# CPU_board_2_7.net
KiCad netlist of a schematic drawn in EAGLE
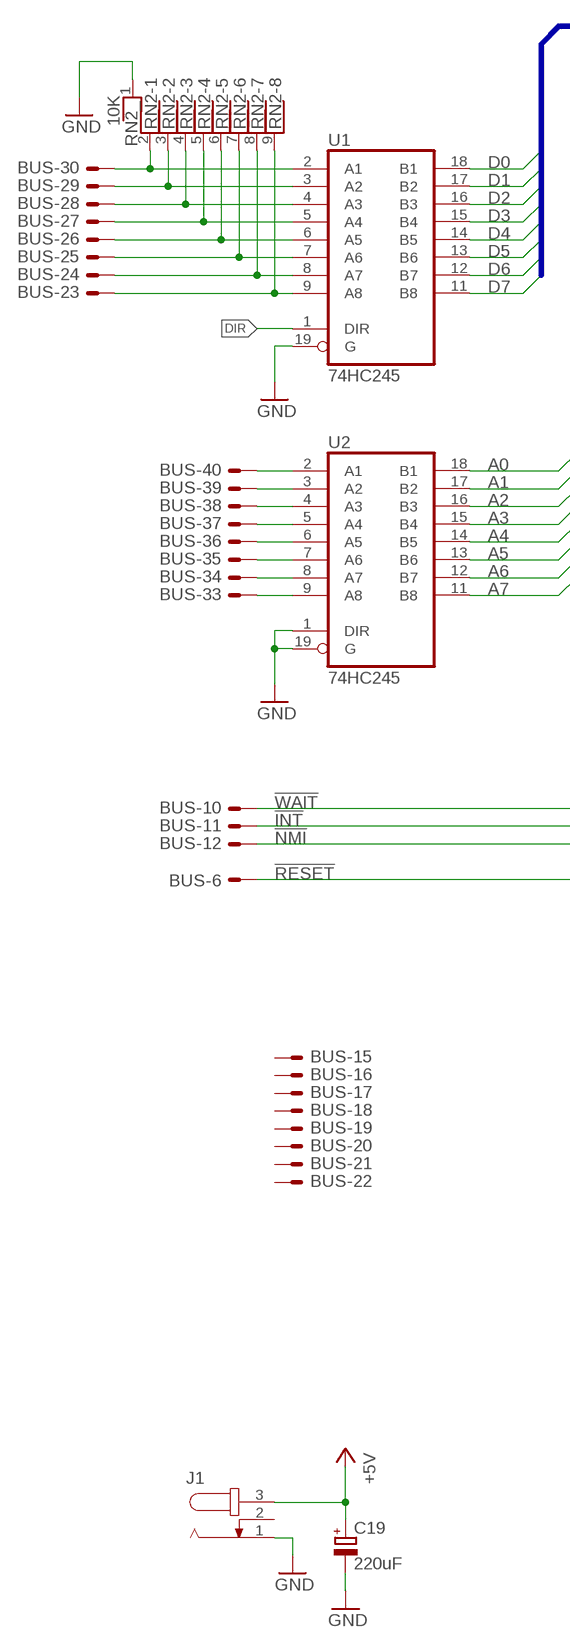
[diagram p0: schematic, sheet 1, part 1 of 2]
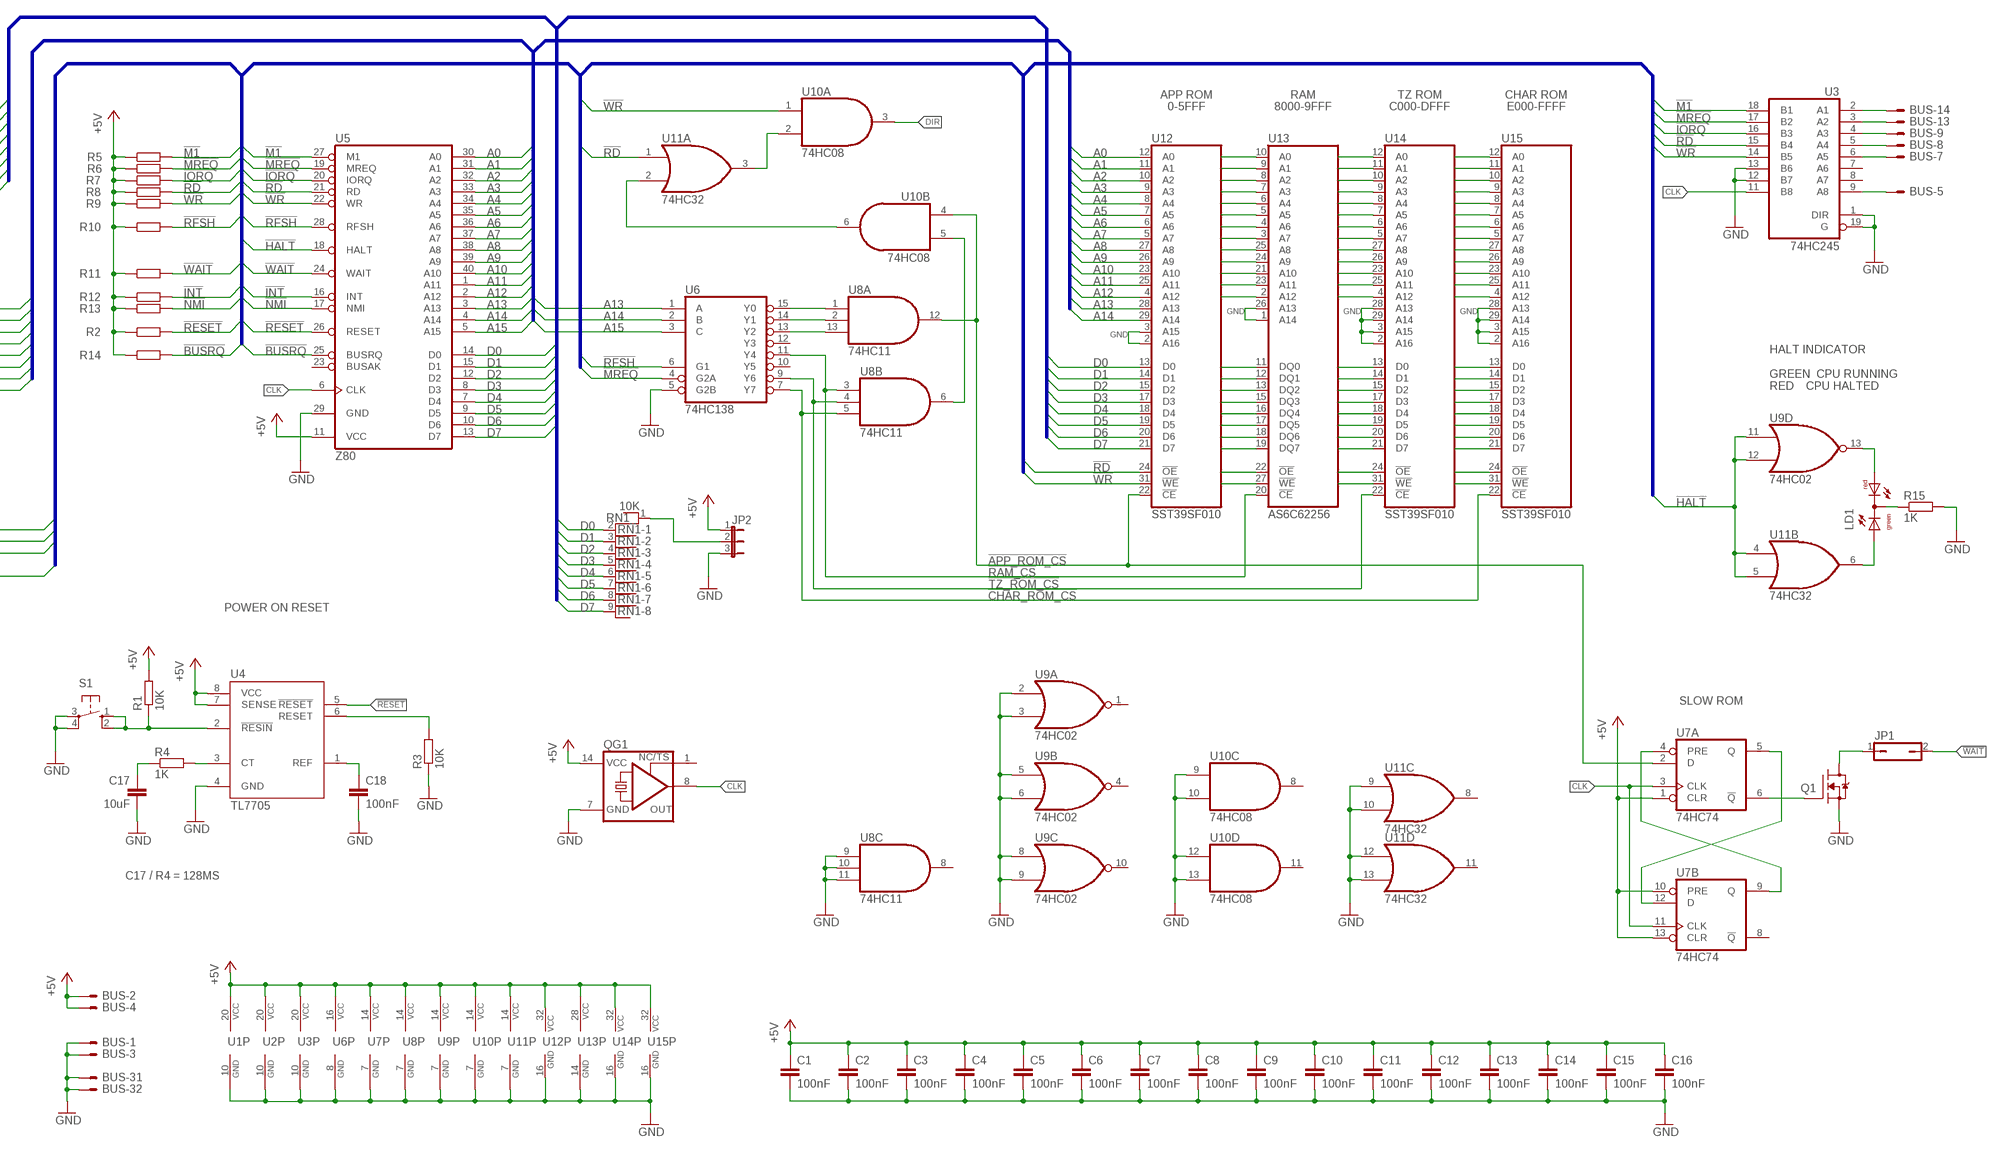
[diagram p1: schematic, sheet 1, part 2 of 2]

(export (version "E")
  (design (tool "Eeschema 10.0.6"))
  (components
    (comp (ref "BUS")
      (value "ML40E")
      (footprint "eagle-import:ML40")
      (libsource (lib "eagle-import") (part "ML40E"))
    )
    (comp (ref "C1")
      (value "100nF")
      (footprint "eagle-import:C050-025X075")
      (libsource (lib "eagle-import") (part "C-EU050-025X075"))
    )
    (comp (ref "C2")
      (value "100nF")
      (footprint "eagle-import:C050-025X075")
      (libsource (lib "eagle-import") (part "C-EU050-025X075"))
    )
    (comp (ref "C3")
      (value "100nF")
      (footprint "eagle-import:C050-025X075")
      (libsource (lib "eagle-import") (part "C-EU050-025X075"))
    )
    (comp (ref "C4")
      (value "100nF")
      (footprint "eagle-import:C050-025X075")
      (libsource (lib "eagle-import") (part "C-EU050-025X075"))
    )
    (comp (ref "C5")
      (value "100nF")
      (footprint "eagle-import:C050-025X075")
      (libsource (lib "eagle-import") (part "C-EU050-025X075"))
    )
    (comp (ref "C6")
      (value "100nF")
      (footprint "eagle-import:C050-025X075")
      (libsource (lib "eagle-import") (part "C-EU050-025X075"))
    )
    (comp (ref "C7")
      (value "100nF")
      (footprint "eagle-import:C050-025X075")
      (libsource (lib "eagle-import") (part "C-EU050-025X075"))
    )
    (comp (ref "C8")
      (value "100nF")
      (footprint "eagle-import:C050-025X075")
      (libsource (lib "eagle-import") (part "C-EU050-025X075"))
    )
    (comp (ref "C9")
      (value "100nF")
      (footprint "eagle-import:C050-025X075")
      (libsource (lib "eagle-import") (part "C-EU050-025X075"))
    )
    (comp (ref "C10")
      (value "100nF")
      (footprint "eagle-import:C050-025X075")
      (libsource (lib "eagle-import") (part "C-EU050-025X075"))
    )
    (comp (ref "C11")
      (value "100nF")
      (footprint "eagle-import:C050-025X075")
      (libsource (lib "eagle-import") (part "C-EU050-025X075"))
    )
    (comp (ref "C12")
      (value "100nF")
      (footprint "eagle-import:C050-025X075")
      (libsource (lib "eagle-import") (part "C-EU050-025X075"))
    )
    (comp (ref "C13")
      (value "100nF")
      (footprint "eagle-import:C050-025X075")
      (libsource (lib "eagle-import") (part "C-EU050-025X075"))
    )
    (comp (ref "C14")
      (value "100nF")
      (footprint "eagle-import:C050-025X075")
      (libsource (lib "eagle-import") (part "C-EU050-025X075"))
    )
    (comp (ref "C15")
      (value "100nF")
      (footprint "eagle-import:C050-025X075")
      (libsource (lib "eagle-import") (part "C-EU050-025X075"))
    )
    (comp (ref "C16")
      (value "100nF")
      (footprint "eagle-import:C050-025X075")
      (libsource (lib "eagle-import") (part "C-EU050-025X075"))
    )
    (comp (ref "C17")
      (value "10uF")
      (footprint "eagle-import:C050-025X075")
      (libsource (lib "eagle-import") (part "C-EU050-025X075"))
    )
    (comp (ref "C18")
      (value "100nF")
      (footprint "eagle-import:C050-025X075")
      (libsource (lib "eagle-import") (part "C-EU050-025X075"))
    )
    (comp (ref "C19")
      (value "220uF")
      (footprint "eagle-import:E3,5-8")
      (libsource (lib "eagle-import") (part "CPOL-EUE3.5-8"))
    )
    (comp (ref "J1")
      (value "JACK-PLUG0")
      (footprint "eagle-import:SPC4077")
      (libsource (lib "eagle-import") (part "JACK-PLUG0"))
    )
    (comp (ref "JP1")
      (value "JP1Q")
      (footprint "eagle-import:JP1")
      (libsource (lib "eagle-import") (part "JP1Q"))
    )
    (comp (ref "JP2")
      (value "JP2E")
      (footprint "eagle-import:JP2")
      (libsource (lib "eagle-import") (part "JP2E"))
    )
    (comp (ref "LD1")
      (value "DUOLED-RG-C")
      (footprint "eagle-import:DUOLED-C-5MM")
      (libsource (lib "eagle-import") (part "DUOLED-RG-C"))
    )
    (comp (ref "Q1")
      (value "2N7000")
      (footprint "eagle-import:TO-92-FORMED")
      (libsource (lib "eagle-import") (part "2N7000"))
    )
    (comp (ref "QG1")
      (value "XO-14")
      (footprint "eagle-import:DIL14S")
      (libsource (lib "eagle-import") (part "XO-14"))
    )
    (comp (ref "R1")
      (value "10K")
      (footprint "eagle-import:0207_10")
      (libsource (lib "eagle-import") (part "R-EU_0207/10"))
    )
    (comp (ref "R2")
      (value "10K")
      (footprint "eagle-import:0207_10")
      (libsource (lib "eagle-import") (part "R-EU_0207/10"))
    )
    (comp (ref "R3")
      (value "10K")
      (footprint "eagle-import:0207_10")
      (libsource (lib "eagle-import") (part "R-EU_0207/10"))
    )
    (comp (ref "R4")
      (value "1K")
      (footprint "eagle-import:0207_10")
      (libsource (lib "eagle-import") (part "R-EU_0207/10"))
    )
    (comp (ref "R5")
      (value "R-EU_0207/10")
      (footprint "eagle-import:0207_10")
      (libsource (lib "eagle-import") (part "R-EU_0207/10"))
    )
    (comp (ref "R6")
      (value "R-EU_0207/10")
      (footprint "eagle-import:0207_10")
      (libsource (lib "eagle-import") (part "R-EU_0207/10"))
    )
    (comp (ref "R7")
      (value "R-EU_0207/10")
      (footprint "eagle-import:0207_10")
      (libsource (lib "eagle-import") (part "R-EU_0207/10"))
    )
    (comp (ref "R8")
      (value "R-EU_0207/10")
      (footprint "eagle-import:0207_10")
      (libsource (lib "eagle-import") (part "R-EU_0207/10"))
    )
    (comp (ref "R9")
      (value "R-EU_0207/10")
      (footprint "eagle-import:0207_10")
      (libsource (lib "eagle-import") (part "R-EU_0207/10"))
    )
    (comp (ref "R10")
      (value "R-EU_0207/10")
      (footprint "eagle-import:0207_10")
      (libsource (lib "eagle-import") (part "R-EU_0207/10"))
    )
    (comp (ref "R11")
      (value "R-EU_0207/10")
      (footprint "eagle-import:0207_10")
      (libsource (lib "eagle-import") (part "R-EU_0207/10"))
    )
    (comp (ref "R12")
      (value "R-EU_0207/10")
      (footprint "eagle-import:0207_10")
      (libsource (lib "eagle-import") (part "R-EU_0207/10"))
    )
    (comp (ref "R13")
      (value "R-EU_0207/10")
      (footprint "eagle-import:0207_10")
      (libsource (lib "eagle-import") (part "R-EU_0207/10"))
    )
    (comp (ref "R14")
      (value "R-EU_0207/10")
      (footprint "eagle-import:0207_10")
      (libsource (lib "eagle-import") (part "R-EU_0207/10"))
    )
    (comp (ref "R15")
      (value "1K")
      (footprint "eagle-import:0207_10")
      (libsource (lib "eagle-import") (part "R-EU_0207/10"))
    )
    (comp (ref "RN1")
      (value "10K")
      (footprint "eagle-import:RN-9")
      (libsource (lib "eagle-import") (part "RNX8"))
    )
    (comp (ref "RN2")
      (value "10K")
      (footprint "eagle-import:RN-9")
      (libsource (lib "eagle-import") (part "RNX8"))
    )
    (comp (ref "S1")
      (value "10-XX")
      (footprint "eagle-import:B3F-10XX")
      (fields (field (name "MPN") "B3F-1000"))
      (libsource (lib "eagle-import") (part "10-XX"))
    )
    (comp (ref "U1")
      (value "74HC245")
      (footprint "eagle-import:DIL20")
      (libsource (lib "eagle-import") (part "74245NLS"))
    )
    (comp (ref "U2")
      (value "74HC245")
      (footprint "eagle-import:DIL20")
      (libsource (lib "eagle-import") (part "74245NLS"))
    )
    (comp (ref "U3")
      (value "74HC245")
      (footprint "eagle-import:DIL20")
      (libsource (lib "eagle-import") (part "74245NLS"))
    )
    (comp (ref "U4")
      (value "TL7705")
      (footprint "eagle-import:DIL08")
      (libsource (lib "eagle-import") (part "TL77XXA"))
    )
    (comp (ref "U5")
      (value "Z80")
      (footprint "eagle-import:DIL40")
      (libsource (lib "eagle-import") (part "Z80CPU"))
    )
    (comp (ref "U6")
      (value "74HC138")
      (footprint "eagle-import:DIL16")
      (libsource (lib "eagle-import") (part "74138NLS"))
    )
    (comp (ref "U7")
      (value "74HC74")
      (footprint "eagle-import:DIL14")
      (libsource (lib "eagle-import") (part "7474NLS"))
    )
    (comp (ref "U8")
      (value "74HC11")
      (footprint "eagle-import:DIL14")
      (libsource (lib "eagle-import") (part "7411NLS"))
    )
    (comp (ref "U9")
      (value "74HC02")
      (footprint "eagle-import:DIL14")
      (libsource (lib "eagle-import") (part "7402NLS"))
    )
    (comp (ref "U10")
      (value "74HC08")
      (footprint "eagle-import:DIL14")
      (libsource (lib "eagle-import") (part "7408NLS"))
    )
    (comp (ref "U11")
      (value "74HC32")
      (footprint "eagle-import:DIL14")
      (libsource (lib "eagle-import") (part "7432NLS"))
    )
    (comp (ref "U12")
      (value "SST39SF010")
      (footprint "eagle-import:DIL32")
      (libsource (lib "eagle-import") (part "SST39SF010P"))
    )
    (comp (ref "U13")
      (value "AS6C62256")
      (footprint "eagle-import:DIL28-6")
      (libsource (lib "eagle-import") (part "AS6C62256-55PCN"))
    )
    (comp (ref "U14")
      (value "SST39SF010")
      (footprint "eagle-import:PLCC-SR32")
      (libsource (lib "eagle-import") (part "SST39SF010NS"))
    )
    (comp (ref "U15")
      (value "SST39SF010")
      (footprint "eagle-import:PLCC-SR32")
      (libsource (lib "eagle-import") (part "SST39SF010NS"))
    )
  )
  (nets
    (net (code "18") (name "+5V") (class "Default")
      (node (ref "BUS") (pin "2") (pinfunction "S_2") (pintype "passive"))
      (node (ref "BUS") (pin "4") (pinfunction "S_4") (pintype "passive"))
      (node (ref "C1") (pin "1") (pinfunction "1_1") (pintype "passive"))
      (node (ref "C10") (pin "1") (pinfunction "1_1") (pintype "passive"))
      (node (ref "C11") (pin "1") (pinfunction "1_1") (pintype "passive"))
      (node (ref "C12") (pin "1") (pinfunction "1_1") (pintype "passive"))
      (node (ref "C13") (pin "1") (pinfunction "1_1") (pintype "passive"))
      (node (ref "C14") (pin "1") (pinfunction "1_1") (pintype "passive"))
      (node (ref "C15") (pin "1") (pinfunction "1_1") (pintype "passive"))
      (node (ref "C16") (pin "1") (pinfunction "1_1") (pintype "passive"))
      (node (ref "C19") (pin "+") (pinfunction "+_+") (pintype "passive"))
      (node (ref "C2") (pin "1") (pinfunction "1_1") (pintype "passive"))
      (node (ref "C3") (pin "1") (pinfunction "1_1") (pintype "passive"))
      (node (ref "C4") (pin "1") (pinfunction "1_1") (pintype "passive"))
      (node (ref "C5") (pin "1") (pinfunction "1_1") (pintype "passive"))
      (node (ref "C6") (pin "1") (pinfunction "1_1") (pintype "passive"))
      (node (ref "C7") (pin "1") (pinfunction "1_1") (pintype "passive"))
      (node (ref "C8") (pin "1") (pinfunction "1_1") (pintype "passive"))
      (node (ref "C9") (pin "1") (pinfunction "1_1") (pintype "passive"))
      (node (ref "J1") (pin "3") (pinfunction "3_3") (pintype "passive"))
      (node (ref "JP2") (pin "1") (pinfunction "1_1") (pintype "passive"))
      (node (ref "QG1") (pin "14") (pinfunction "VCC_14") (pintype "power_in"))
      (node (ref "R1") (pin "2") (pinfunction "2_2") (pintype "passive"))
      (node (ref "R10") (pin "1") (pinfunction "1_1") (pintype "passive"))
      (node (ref "R11") (pin "1") (pinfunction "1_1") (pintype "passive"))
      (node (ref "R12") (pin "1") (pinfunction "1_1") (pintype "passive"))
      (node (ref "R13") (pin "1") (pinfunction "1_1") (pintype "passive"))
      (node (ref "R14") (pin "1") (pinfunction "1_1") (pintype "passive"))
      (node (ref "R2") (pin "1") (pinfunction "1_1") (pintype "passive"))
      (node (ref "R5") (pin "1") (pinfunction "1_1") (pintype "passive"))
      (node (ref "R6") (pin "1") (pinfunction "1_1") (pintype "passive"))
      (node (ref "R7") (pin "1") (pinfunction "1_1") (pintype "passive"))
      (node (ref "R8") (pin "1") (pinfunction "1_1") (pintype "passive"))
      (node (ref "R9") (pin "1") (pinfunction "1_1") (pintype "passive"))
      (node (ref "U1") (pin "20") (pinfunction "VCC_20") (pintype "power_in"))
      (node (ref "U10") (pin "14") (pinfunction "VCC_14") (pintype "power_in"))
      (node (ref "U11") (pin "14") (pinfunction "VCC_14") (pintype "power_in"))
      (node (ref "U12") (pin "32") (pinfunction "VCC_32") (pintype "power_in"))
      (node (ref "U13") (pin "28") (pinfunction "VCC_28") (pintype "power_in"))
      (node (ref "U14") (pin "32") (pinfunction "VCC_32") (pintype "power_in"))
      (node (ref "U15") (pin "32") (pinfunction "VCC_32") (pintype "power_in"))
      (node (ref "U2") (pin "20") (pinfunction "VCC_20") (pintype "power_in"))
      (node (ref "U3") (pin "20") (pinfunction "VCC_20") (pintype "power_in"))
      (node (ref "U4") (pin "7") (pinfunction "SENSE_7") (pintype "input"))
      (node (ref "U4") (pin "8") (pinfunction "VCC_8") (pintype "power_in"))
      (node (ref "U5") (pin "11") (pinfunction "VCC_11") (pintype "power_in"))
      (node (ref "U6") (pin "16") (pinfunction "VCC_16") (pintype "power_in"))
      (node (ref "U7") (pin "1") (pinfunction "CLR_1") (pintype "input"))
      (node (ref "U7") (pin "10") (pinfunction "PRE_10") (pintype "input"))
      (node (ref "U7") (pin "13") (pinfunction "CLR_13") (pintype "input"))
      (node (ref "U7") (pin "14") (pinfunction "VCC_14") (pintype "power_in"))
      (node (ref "U8") (pin "14") (pinfunction "VCC_14") (pintype "power_in"))
      (node (ref "U9") (pin "14") (pinfunction "VCC_14") (pintype "power_in"))
    )
    (net (code "21") (name "A0") (class "Default")
      (node (ref "U12") (pin "12") (pinfunction "A0_12") (pintype "input"))
      (node (ref "U13") (pin "10") (pinfunction "A0_10") (pintype "input"))
      (node (ref "U14") (pin "12") (pinfunction "A0_12") (pintype "input"))
      (node (ref "U15") (pin "12") (pinfunction "A0_12") (pintype "input"))
      (node (ref "U2") (pin "18") (pinfunction "B1_18") (pintype "bidirectional"))
      (node (ref "U5") (pin "30") (pinfunction "A0_30") (pintype "output"))
    )
    (net (code "22") (name "A1") (class "Default")
      (node (ref "U12") (pin "11") (pinfunction "A1_11") (pintype "input"))
      (node (ref "U13") (pin "9") (pinfunction "A1_9") (pintype "input"))
      (node (ref "U14") (pin "11") (pinfunction "A1_11") (pintype "input"))
      (node (ref "U15") (pin "11") (pinfunction "A1_11") (pintype "input"))
      (node (ref "U2") (pin "17") (pinfunction "B2_17") (pintype "bidirectional"))
      (node (ref "U5") (pin "31") (pinfunction "A1_31") (pintype "output"))
    )
    (net (code "23") (name "A2") (class "Default")
      (node (ref "U12") (pin "10") (pinfunction "A2_10") (pintype "input"))
      (node (ref "U13") (pin "8") (pinfunction "A2_8") (pintype "input"))
      (node (ref "U14") (pin "10") (pinfunction "A2_10") (pintype "input"))
      (node (ref "U15") (pin "10") (pinfunction "A2_10") (pintype "input"))
      (node (ref "U2") (pin "16") (pinfunction "B3_16") (pintype "bidirectional"))
      (node (ref "U5") (pin "32") (pinfunction "A2_32") (pintype "output"))
    )
    (net (code "24") (name "A3") (class "Default")
      (node (ref "U12") (pin "9") (pinfunction "A3_9") (pintype "input"))
      (node (ref "U13") (pin "7") (pinfunction "A3_7") (pintype "input"))
      (node (ref "U14") (pin "9") (pinfunction "A3_9") (pintype "input"))
      (node (ref "U15") (pin "9") (pinfunction "A3_9") (pintype "input"))
      (node (ref "U2") (pin "15") (pinfunction "B4_15") (pintype "bidirectional"))
      (node (ref "U5") (pin "33") (pinfunction "A3_33") (pintype "output"))
    )
    (net (code "25") (name "A4") (class "Default")
      (node (ref "U12") (pin "8") (pinfunction "A4_8") (pintype "input"))
      (node (ref "U13") (pin "6") (pinfunction "A4_6") (pintype "input"))
      (node (ref "U14") (pin "8") (pinfunction "A4_8") (pintype "input"))
      (node (ref "U15") (pin "8") (pinfunction "A4_8") (pintype "input"))
      (node (ref "U2") (pin "14") (pinfunction "B5_14") (pintype "bidirectional"))
      (node (ref "U5") (pin "34") (pinfunction "A4_34") (pintype "output"))
    )
    (net (code "26") (name "A5") (class "Default")
      (node (ref "U12") (pin "7") (pinfunction "A5_7") (pintype "input"))
      (node (ref "U13") (pin "5") (pinfunction "A5_5") (pintype "input"))
      (node (ref "U14") (pin "7") (pinfunction "A5_7") (pintype "input"))
      (node (ref "U15") (pin "7") (pinfunction "A5_7") (pintype "input"))
      (node (ref "U2") (pin "13") (pinfunction "B6_13") (pintype "bidirectional"))
      (node (ref "U5") (pin "35") (pinfunction "A5_35") (pintype "output"))
    )
    (net (code "27") (name "A6") (class "Default")
      (node (ref "U12") (pin "6") (pinfunction "A6_6") (pintype "input"))
      (node (ref "U13") (pin "4") (pinfunction "A6_4") (pintype "input"))
      (node (ref "U14") (pin "6") (pinfunction "A6_6") (pintype "input"))
      (node (ref "U15") (pin "6") (pinfunction "A6_6") (pintype "input"))
      (node (ref "U2") (pin "12") (pinfunction "B7_12") (pintype "bidirectional"))
      (node (ref "U5") (pin "36") (pinfunction "A6_36") (pintype "output"))
    )
    (net (code "28") (name "A7") (class "Default")
      (node (ref "U12") (pin "5") (pinfunction "A7_5") (pintype "input"))
      (node (ref "U13") (pin "3") (pinfunction "A7_3") (pintype "input"))
      (node (ref "U14") (pin "5") (pinfunction "A7_5") (pintype "input"))
      (node (ref "U15") (pin "5") (pinfunction "A7_5") (pintype "input"))
      (node (ref "U2") (pin "11") (pinfunction "B8_11") (pintype "bidirectional"))
      (node (ref "U5") (pin "37") (pinfunction "A7_37") (pintype "output"))
    )
    (net (code "29") (name "A8") (class "Default")
      (node (ref "U12") (pin "27") (pinfunction "A8_27") (pintype "input"))
      (node (ref "U13") (pin "25") (pinfunction "A8_25") (pintype "input"))
      (node (ref "U14") (pin "27") (pinfunction "A8_27") (pintype "input"))
      (node (ref "U15") (pin "27") (pinfunction "A8_27") (pintype "input"))
      (node (ref "U5") (pin "38") (pinfunction "A8_38") (pintype "output"))
    )
    (net (code "30") (name "A9") (class "Default")
      (node (ref "U12") (pin "26") (pinfunction "A9_26") (pintype "input"))
      (node (ref "U13") (pin "24") (pinfunction "A9_24") (pintype "input"))
      (node (ref "U14") (pin "26") (pinfunction "A9_26") (pintype "input"))
      (node (ref "U15") (pin "26") (pinfunction "A9_26") (pintype "input"))
      (node (ref "U5") (pin "39") (pinfunction "A9_39") (pintype "output"))
    )
    (net (code "31") (name "A10") (class "Default")
      (node (ref "U12") (pin "23") (pinfunction "A10_23") (pintype "input"))
      (node (ref "U13") (pin "21") (pinfunction "A10_21") (pintype "input"))
      (node (ref "U14") (pin "23") (pinfunction "A10_23") (pintype "input"))
      (node (ref "U15") (pin "23") (pinfunction "A10_23") (pintype "input"))
      (node (ref "U5") (pin "40") (pinfunction "A10_40") (pintype "output"))
    )
    (net (code "32") (name "A11") (class "Default")
      (node (ref "U12") (pin "25") (pinfunction "A11_25") (pintype "input"))
      (node (ref "U13") (pin "23") (pinfunction "A11_23") (pintype "input"))
      (node (ref "U14") (pin "25") (pinfunction "A11_25") (pintype "input"))
      (node (ref "U15") (pin "25") (pinfunction "A11_25") (pintype "input"))
      (node (ref "U5") (pin "1") (pinfunction "A11_1") (pintype "output"))
    )
    (net (code "33") (name "A12") (class "Default")
      (node (ref "U12") (pin "4") (pinfunction "A12_4") (pintype "input"))
      (node (ref "U13") (pin "2") (pinfunction "A12_2") (pintype "input"))
      (node (ref "U14") (pin "4") (pinfunction "A12_4") (pintype "input"))
      (node (ref "U15") (pin "4") (pinfunction "A12_4") (pintype "input"))
      (node (ref "U5") (pin "2") (pinfunction "A12_2") (pintype "output"))
    )
    (net (code "34") (name "A13") (class "Default")
      (node (ref "U12") (pin "28") (pinfunction "A13_28") (pintype "input"))
      (node (ref "U5") (pin "3") (pinfunction "A13_3") (pintype "output"))
      (node (ref "U6") (pin "1") (pinfunction "A_1") (pintype "input"))
    )
    (net (code "35") (name "A14") (class "Default")
      (node (ref "U12") (pin "29") (pinfunction "A14_29") (pintype "input"))
      (node (ref "U5") (pin "4") (pinfunction "A14_4") (pintype "output"))
      (node (ref "U6") (pin "2") (pinfunction "B_2") (pintype "input"))
    )
    (net (code "36") (name "A15") (class "Default")
      (node (ref "U5") (pin "5") (pinfunction "A15_5") (pintype "output"))
      (node (ref "U6") (pin "3") (pinfunction "C_3") (pintype "input"))
    )
    (net (code "37") (name "CLK") (class "Default")
      (node (ref "QG1") (pin "8") (pinfunction "OUT_8") (pintype "output"))
      (node (ref "U3") (pin "11") (pinfunction "B8_11") (pintype "bidirectional"))
      (node (ref "U5") (pin "6") (pinfunction "CLK_6") (pintype "input"))
      (node (ref "U7") (pin "11") (pinfunction "CLK_11") (pintype "input"))
      (node (ref "U7") (pin "3") (pinfunction "CLK_3") (pintype "input"))
    )
    (net (code "38") (name "D0") (class "Default")
      (node (ref "RN1") (pin "2") (pinfunction "1_2") (pintype "passive"))
      (node (ref "U1") (pin "18") (pinfunction "B1_18") (pintype "bidirectional"))
      (node (ref "U12") (pin "13") (pinfunction "D0_13") (pintype "bidirectional"))
      (node (ref "U13") (pin "11") (pinfunction "DQ0_11") (pintype "bidirectional"))
      (node (ref "U14") (pin "13") (pinfunction "D0_13") (pintype "bidirectional"))
      (node (ref "U15") (pin "13") (pinfunction "D0_13") (pintype "bidirectional"))
      (node (ref "U5") (pin "14") (pinfunction "D0_14") (pintype "bidirectional"))
    )
    (net (code "39") (name "D1") (class "Default")
      (node (ref "RN1") (pin "3") (pinfunction "1_3") (pintype "passive"))
      (node (ref "U1") (pin "17") (pinfunction "B2_17") (pintype "bidirectional"))
      (node (ref "U12") (pin "14") (pinfunction "D1_14") (pintype "bidirectional"))
      (node (ref "U13") (pin "12") (pinfunction "DQ1_12") (pintype "bidirectional"))
      (node (ref "U14") (pin "14") (pinfunction "D1_14") (pintype "bidirectional"))
      (node (ref "U15") (pin "14") (pinfunction "D1_14") (pintype "bidirectional"))
      (node (ref "U5") (pin "15") (pinfunction "D1_15") (pintype "bidirectional"))
    )
    (net (code "40") (name "D2") (class "Default")
      (node (ref "RN1") (pin "4") (pinfunction "1_4") (pintype "passive"))
      (node (ref "U1") (pin "16") (pinfunction "B3_16") (pintype "bidirectional"))
      (node (ref "U12") (pin "15") (pinfunction "D2_15") (pintype "bidirectional"))
      (node (ref "U13") (pin "13") (pinfunction "DQ2_13") (pintype "bidirectional"))
      (node (ref "U14") (pin "15") (pinfunction "D2_15") (pintype "bidirectional"))
      (node (ref "U15") (pin "15") (pinfunction "D2_15") (pintype "bidirectional"))
      (node (ref "U5") (pin "12") (pinfunction "D2_12") (pintype "bidirectional"))
    )
    (net (code "41") (name "D3") (class "Default")
      (node (ref "RN1") (pin "5") (pinfunction "1_5") (pintype "passive"))
      (node (ref "U1") (pin "15") (pinfunction "B4_15") (pintype "bidirectional"))
      (node (ref "U12") (pin "17") (pinfunction "D3_17") (pintype "bidirectional"))
      (node (ref "U13") (pin "15") (pinfunction "DQ3_15") (pintype "bidirectional"))
      (node (ref "U14") (pin "17") (pinfunction "D3_17") (pintype "bidirectional"))
      (node (ref "U15") (pin "17") (pinfunction "D3_17") (pintype "bidirectional"))
      (node (ref "U5") (pin "8") (pinfunction "D3_8") (pintype "bidirectional"))
    )
    (net (code "42") (name "D4") (class "Default")
      (node (ref "RN1") (pin "6") (pinfunction "1_6") (pintype "passive"))
      (node (ref "U1") (pin "14") (pinfunction "B5_14") (pintype "bidirectional"))
      (node (ref "U12") (pin "18") (pinfunction "D4_18") (pintype "bidirectional"))
      (node (ref "U13") (pin "16") (pinfunction "DQ4_16") (pintype "bidirectional"))
      (node (ref "U14") (pin "18") (pinfunction "D4_18") (pintype "bidirectional"))
      (node (ref "U15") (pin "18") (pinfunction "D4_18") (pintype "bidirectional"))
      (node (ref "U5") (pin "7") (pinfunction "D4_7") (pintype "bidirectional"))
    )
    (net (code "43") (name "D5") (class "Default")
      (node (ref "RN1") (pin "7") (pinfunction "1_7") (pintype "passive"))
      (node (ref "U1") (pin "13") (pinfunction "B6_13") (pintype "bidirectional"))
      (node (ref "U12") (pin "19") (pinfunction "D5_19") (pintype "bidirectional"))
      (node (ref "U13") (pin "17") (pinfunction "DQ5_17") (pintype "bidirectional"))
      (node (ref "U14") (pin "19") (pinfunction "D5_19") (pintype "bidirectional"))
      (node (ref "U15") (pin "19") (pinfunction "D5_19") (pintype "bidirectional"))
      (node (ref "U5") (pin "9") (pinfunction "D5_9") (pintype "bidirectional"))
    )
    (net (code "44") (name "D6") (class "Default")
      (node (ref "RN1") (pin "8") (pinfunction "1_8") (pintype "passive"))
      (node (ref "U1") (pin "12") (pinfunction "B7_12") (pintype "bidirectional"))
      (node (ref "U12") (pin "20") (pinfunction "D6_20") (pintype "bidirectional"))
      (node (ref "U13") (pin "18") (pinfunction "DQ6_18") (pintype "bidirectional"))
      (node (ref "U14") (pin "20") (pinfunction "D6_20") (pintype "bidirectional"))
      (node (ref "U15") (pin "20") (pinfunction "D6_20") (pintype "bidirectional"))
      (node (ref "U5") (pin "10") (pinfunction "D6_10") (pintype "bidirectional"))
    )
    (net (code "45") (name "D7") (class "Default")
      (node (ref "RN1") (pin "9") (pinfunction "1_9") (pintype "passive"))
      (node (ref "U1") (pin "11") (pinfunction "B8_11") (pintype "bidirectional"))
      (node (ref "U12") (pin "21") (pinfunction "D7_21") (pintype "bidirectional"))
      (node (ref "U13") (pin "19") (pinfunction "DQ7_19") (pintype "bidirectional"))
      (node (ref "U14") (pin "21") (pinfunction "D7_21") (pintype "bidirectional"))
      (node (ref "U15") (pin "21") (pinfunction "D7_21") (pintype "bidirectional"))
      (node (ref "U5") (pin "13") (pinfunction "D7_13") (pintype "bidirectional"))
    )
    (net (code "46") (name "DIR") (class "Default")
      (node (ref "U1") (pin "1") (pinfunction "DIR_1") (pintype "input"))
      (node (ref "U10") (pin "3") (pinfunction "O_3") (pintype "output"))
    )
    (net (code "47") (name "GND") (class "Default")
      (node (ref "BUS") (pin "1") (pinfunction "S_1") (pintype "passive"))
      (node (ref "BUS") (pin "3") (pinfunction "S_3") (pintype "passive"))
      (node (ref "BUS") (pin "31") (pinfunction "S_31") (pintype "passive"))
      (node (ref "BUS") (pin "32") (pinfunction "S_32") (pintype "passive"))
      (node (ref "C1") (pin "2") (pinfunction "2_2") (pintype "passive"))
      (node (ref "C10") (pin "2") (pinfunction "2_2") (pintype "passive"))
      (node (ref "C11") (pin "2") (pinfunction "2_2") (pintype "passive"))
      (node (ref "C12") (pin "2") (pinfunction "2_2") (pintype "passive"))
      (node (ref "C13") (pin "2") (pinfunction "2_2") (pintype "passive"))
      (node (ref "C14") (pin "2") (pinfunction "2_2") (pintype "passive"))
      (node (ref "C15") (pin "2") (pinfunction "2_2") (pintype "passive"))
      (node (ref "C16") (pin "2") (pinfunction "2_2") (pintype "passive"))
      (node (ref "C17") (pin "2") (pinfunction "2_2") (pintype "passive"))
      (node (ref "C18") (pin "2") (pinfunction "2_2") (pintype "passive"))
      (node (ref "C19") (pin "-") (pinfunction "-_-") (pintype "passive"))
      (node (ref "C2") (pin "2") (pinfunction "2_2") (pintype "passive"))
      (node (ref "C3") (pin "2") (pinfunction "2_2") (pintype "passive"))
      (node (ref "C4") (pin "2") (pinfunction "2_2") (pintype "passive"))
      (node (ref "C5") (pin "2") (pinfunction "2_2") (pintype "passive"))
      (node (ref "C6") (pin "2") (pinfunction "2_2") (pintype "passive"))
      (node (ref "C7") (pin "2") (pinfunction "2_2") (pintype "passive"))
      (node (ref "C8") (pin "2") (pinfunction "2_2") (pintype "passive"))
      (node (ref "C9") (pin "2") (pinfunction "2_2") (pintype "passive"))
      (node (ref "J1") (pin "1") (pinfunction "1_1") (pintype "passive"))
      (node (ref "JP2") (pin "3") (pinfunction "3_3") (pintype "passive"))
      (node (ref "Q1") (pin "1") (pinfunction "S_1") (pintype "passive"))
      (node (ref "QG1") (pin "7") (pinfunction "GND_7") (pintype "power_in"))
      (node (ref "R15") (pin "2") (pinfunction "2_2") (pintype "passive"))
      (node (ref "R3") (pin "1") (pinfunction "1_1") (pintype "passive"))
      (node (ref "RN2") (pin "1") (pinfunction "1_1") (pintype "passive"))
      (node (ref "S1") (pin "3") (pinfunction "P_3") (pintype "passive"))
      (node (ref "S1") (pin "4") (pinfunction "P1_4") (pintype "passive"))
      (node (ref "U1") (pin "10") (pinfunction "GND_10") (pintype "power_in"))
      (node (ref "U1") (pin "19") (pinfunction "G_19") (pintype "input"))
      (node (ref "U10") (pin "10") (pinfunction "I1_10") (pintype "input"))
      (node (ref "U10") (pin "12") (pinfunction "I0_12") (pintype "input"))
      (node (ref "U10") (pin "13") (pinfunction "I1_13") (pintype "input"))
      (node (ref "U10") (pin "7") (pinfunction "GND_7") (pintype "power_in"))
      (node (ref "U10") (pin "9") (pinfunction "I0_9") (pintype "input"))
      (node (ref "U11") (pin "10") (pinfunction "I1_10") (pintype "input"))
      (node (ref "U11") (pin "12") (pinfunction "I0_12") (pintype "input"))
      (node (ref "U11") (pin "13") (pinfunction "I1_13") (pintype "input"))
      (node (ref "U11") (pin "7") (pinfunction "GND_7") (pintype "power_in"))
      (node (ref "U11") (pin "9") (pinfunction "I0_9") (pintype "input"))
      (node (ref "U12") (pin "16") (pinfunction "GND_16") (pintype "power_in"))
      (node (ref "U12") (pin "2") (pinfunction "A16_2") (pintype "input"))
      (node (ref "U12") (pin "3") (pinfunction "A15_3") (pintype "input"))
      (node (ref "U13") (pin "1") (pinfunction "A14_1") (pintype "input"))
      (node (ref "U13") (pin "14") (pinfunction "GND_14") (pintype "power_in"))
      (node (ref "U13") (pin "26") (pinfunction "A13_26") (pintype "input"))
      (node (ref "U14") (pin "16") (pinfunction "GND_16") (pintype "power_in"))
      (node (ref "U14") (pin "2") (pinfunction "A16_2") (pintype "input"))
      (node (ref "U14") (pin "28") (pinfunction "A13_28") (pintype "input"))
      (node (ref "U14") (pin "29") (pinfunction "A14_29") (pintype "input"))
      (node (ref "U14") (pin "3") (pinfunction "A15_3") (pintype "input"))
      (node (ref "U15") (pin "16") (pinfunction "GND_16") (pintype "power_in"))
      (node (ref "U15") (pin "2") (pinfunction "A16_2") (pintype "input"))
      (node (ref "U15") (pin "28") (pinfunction "A13_28") (pintype "input"))
      (node (ref "U15") (pin "29") (pinfunction "A14_29") (pintype "input"))
      (node (ref "U15") (pin "3") (pinfunction "A15_3") (pintype "input"))
      (node (ref "U2") (pin "1") (pinfunction "DIR_1") (pintype "input"))
      (node (ref "U2") (pin "10") (pinfunction "GND_10") (pintype "power_in"))
      (node (ref "U2") (pin "19") (pinfunction "G_19") (pintype "input"))
      (node (ref "U3") (pin "1") (pinfunction "DIR_1") (pintype "input"))
      (node (ref "U3") (pin "10") (pinfunction "GND_10") (pintype "power_in"))
      (node (ref "U3") (pin "12") (pinfunction "B7_12") (pintype "bidirectional"))
      (node (ref "U3") (pin "13") (pinfunction "B6_13") (pintype "bidirectional"))
      (node (ref "U3") (pin "19") (pinfunction "G_19") (pintype "input"))
      (node (ref "U4") (pin "4") (pinfunction "GND_4") (pintype "power_in"))
      (node (ref "U5") (pin "29") (pinfunction "GND_29") (pintype "power_in"))
      (node (ref "U6") (pin "5") (pinfunction "G2B_5") (pintype "input"))
      (node (ref "U6") (pin "8") (pinfunction "GND_8") (pintype "power_in"))
      (node (ref "U7") (pin "7") (pinfunction "GND_7") (pintype "power_in"))
      (node (ref "U8") (pin "10") (pinfunction "I1_10") (pintype "input"))
      (node (ref "U8") (pin "11") (pinfunction "I2_11") (pintype "input"))
      (node (ref "U8") (pin "7") (pinfunction "GND_7") (pintype "power_in"))
      (node (ref "U8") (pin "9") (pinfunction "I0_9") (pintype "input"))
      (node (ref "U9") (pin "2") (pinfunction "I0_2") (pintype "input"))
      (node (ref "U9") (pin "3") (pinfunction "I1_3") (pintype "input"))
      (node (ref "U9") (pin "5") (pinfunction "I0_5") (pintype "input"))
      (node (ref "U9") (pin "6") (pinfunction "I1_6") (pintype "input"))
      (node (ref "U9") (pin "7") (pinfunction "GND_7") (pintype "power_in"))
      (node (ref "U9") (pin "8") (pinfunction "I0_8") (pintype "input"))
      (node (ref "U9") (pin "9") (pinfunction "I1_9") (pintype "input"))
    )
    (net (code "48") (name "Net-(BUSAA-S)") (class "Default")
      (node (ref "BUS") (pin "33") (pinfunction "S_33") (pintype "passive"))
      (node (ref "U2") (pin "9") (pinfunction "A8_9") (pintype "bidirectional"))
    )
    (net (code "49") (name "Net-(BUSAB-S)") (class "Default")
      (node (ref "BUS") (pin "34") (pinfunction "S_34") (pintype "passive"))
      (node (ref "U2") (pin "8") (pinfunction "A7_8") (pintype "bidirectional"))
    )
    (net (code "50") (name "Net-(BUSAC-S)") (class "Default")
      (node (ref "BUS") (pin "35") (pinfunction "S_35") (pintype "passive"))
      (node (ref "U2") (pin "7") (pinfunction "A6_7") (pintype "bidirectional"))
    )
    (net (code "51") (name "Net-(BUSAD-S)") (class "Default")
      (node (ref "BUS") (pin "36") (pinfunction "S_36") (pintype "passive"))
      (node (ref "U2") (pin "6") (pinfunction "A5_6") (pintype "bidirectional"))
    )
    (net (code "52") (name "Net-(BUSAE-S)") (class "Default")
      (node (ref "BUS") (pin "37") (pinfunction "S_37") (pintype "passive"))
      (node (ref "U2") (pin "5") (pinfunction "A4_5") (pintype "bidirectional"))
    )
    (net (code "53") (name "Net-(BUSAF-S)") (class "Default")
      (node (ref "BUS") (pin "38") (pinfunction "S_38") (pintype "passive"))
      (node (ref "U2") (pin "4") (pinfunction "A3_4") (pintype "bidirectional"))
    )
    (net (code "54") (name "Net-(BUSAG-S)") (class "Default")
      (node (ref "BUS") (pin "39") (pinfunction "S_39") (pintype "passive"))
      (node (ref "U2") (pin "3") (pinfunction "A2_3") (pintype "bidirectional"))
    )
    (net (code "55") (name "Net-(BUSAI-S)") (class "Default")
      (node (ref "BUS") (pin "40") (pinfunction "S_40") (pintype "passive"))
      (node (ref "U2") (pin "2") (pinfunction "A1_2") (pintype "bidirectional"))
    )
    (net (code "56") (name "Net-(BUSAJ-S)") (class "Default")
      (node (ref "BUS") (pin "5") (pinfunction "S_5") (pintype "passive"))
      (node (ref "U3") (pin "9") (pinfunction "A8_9") (pintype "bidirectional"))
    )
    (net (code "57") (name "Net-(BUSAL-S)") (class "Default")
      (node (ref "BUS") (pin "7") (pinfunction "S_7") (pintype "passive"))
      (node (ref "U3") (pin "6") (pinfunction "A5_6") (pintype "bidirectional"))
    )
    (net (code "58") (name "Net-(BUSAM-S)") (class "Default")
      (node (ref "BUS") (pin "8") (pinfunction "S_8") (pintype "passive"))
      (node (ref "U3") (pin "5") (pinfunction "A4_5") (pintype "bidirectional"))
    )
    (net (code "59") (name "Net-(BUSAN-S)") (class "Default")
      (node (ref "BUS") (pin "9") (pinfunction "S_9") (pintype "passive"))
      (node (ref "U3") (pin "4") (pinfunction "A3_4") (pintype "bidirectional"))
    )
    (net (code "60") (name "Net-(BUSE-S)") (class "Default")
      (node (ref "BUS") (pin "13") (pinfunction "S_13") (pintype "passive"))
      (node (ref "U3") (pin "3") (pinfunction "A2_3") (pintype "bidirectional"))
    )
    (net (code "61") (name "Net-(BUSF-S)") (class "Default")
      (node (ref "BUS") (pin "14") (pinfunction "S_14") (pintype "passive"))
      (node (ref "U3") (pin "2") (pinfunction "A1_2") (pintype "bidirectional"))
    )
    (net (code "62") (name "Net-(BUSP-S)") (class "Default")
      (node (ref "BUS") (pin "23") (pinfunction "S_23") (pintype "passive"))
      (node (ref "RN2") (pin "9") (pinfunction "1_9") (pintype "passive"))
      (node (ref "U1") (pin "9") (pinfunction "A8_9") (pintype "bidirectional"))
    )
    (net (code "63") (name "Net-(BUSQ-S)") (class "Default")
      (node (ref "BUS") (pin "24") (pinfunction "S_24") (pintype "passive"))
      (node (ref "RN2") (pin "8") (pinfunction "1_8") (pintype "passive"))
      (node (ref "U1") (pin "8") (pinfunction "A7_8") (pintype "bidirectional"))
    )
    (net (code "64") (name "Net-(BUSR-S)") (class "Default")
      (node (ref "BUS") (pin "25") (pinfunction "S_25") (pintype "passive"))
      (node (ref "RN2") (pin "7") (pinfunction "1_7") (pintype "passive"))
      (node (ref "U1") (pin "7") (pinfunction "A6_7") (pintype "bidirectional"))
    )
    (net (code "65") (name "Net-(BUSS-S)") (class "Default")
      (node (ref "BUS") (pin "26") (pinfunction "S_26") (pintype "passive"))
      (node (ref "RN2") (pin "6") (pinfunction "1_6") (pintype "passive"))
      (node (ref "U1") (pin "6") (pinfunction "A5_6") (pintype "bidirectional"))
    )
    (net (code "66") (name "Net-(BUST-S)") (class "Default")
      (node (ref "BUS") (pin "27") (pinfunction "S_27") (pintype "passive"))
      (node (ref "RN2") (pin "5") (pinfunction "1_5") (pintype "passive"))
      (node (ref "U1") (pin "5") (pinfunction "A4_5") (pintype "bidirectional"))
    )
    (net (code "67") (name "Net-(BUSU-S)") (class "Default")
      (node (ref "BUS") (pin "28") (pinfunction "S_28") (pintype "passive"))
      (node (ref "RN2") (pin "4") (pinfunction "1_4") (pintype "passive"))
      (node (ref "U1") (pin "4") (pinfunction "A3_4") (pintype "bidirectional"))
    )
    (net (code "68") (name "Net-(BUSV-S)") (class "Default")
      (node (ref "BUS") (pin "29") (pinfunction "S_29") (pintype "passive"))
      (node (ref "RN2") (pin "3") (pinfunction "1_3") (pintype "passive"))
      (node (ref "U1") (pin "3") (pinfunction "A2_3") (pintype "bidirectional"))
    )
    (net (code "69") (name "Net-(BUSX-S)") (class "Default")
      (node (ref "BUS") (pin "30") (pinfunction "S_30") (pintype "passive"))
      (node (ref "RN2") (pin "2") (pinfunction "1_2") (pintype "passive"))
      (node (ref "U1") (pin "2") (pinfunction "A1_2") (pintype "bidirectional"))
    )
    (net (code "70") (name "Net-(C17-Pad1)") (class "Default")
      (node (ref "C17") (pin "1") (pinfunction "1_1") (pintype "passive"))
      (node (ref "R4") (pin "1") (pinfunction "1_1") (pintype "passive"))
    )
    (net (code "71") (name "Net-(JP2-Pad2)") (class "Default")
      (node (ref "JP2") (pin "2") (pinfunction "2_2") (pintype "passive"))
      (node (ref "RN1") (pin "1") (pinfunction "1_1") (pintype "passive"))
    )
    (net (code "72") (name "Net-(LD1-AG)") (class "Default")
      (node (ref "LD1") (pin "AX") (pinfunction "AG_AX") (pintype "passive"))
      (node (ref "U11") (pin "6") (pinfunction "O_6") (pintype "output"))
    )
    (net (code "73") (name "Net-(LD1-PadC)") (class "Default")
      (node (ref "LD1") (pin "C") (pinfunction "C_C") (pintype "passive"))
      (node (ref "R15") (pin "1") (pinfunction "1_1") (pintype "passive"))
    )
    (net (code "74") (name "Net-(Q1-D)") (class "Default")
      (node (ref "JP1") (pin "1") (pinfunction "1_1") (pintype "passive"))
      (node (ref "Q1") (pin "3") (pinfunction "D_3") (pintype "passive"))
    )
    (net (code "75") (name "Net-(Q1-G)") (class "Default")
      (node (ref "Q1") (pin "2") (pinfunction "G_2") (pintype "passive"))
      (node (ref "U7") (pin "6") (pinfunction "~{Q}_6") (pintype "output"))
    )
    (net (code "76") (name "Net-(S1-S)") (class "Default")
      (node (ref "R1") (pin "1") (pinfunction "1_1") (pintype "passive"))
      (node (ref "S1") (pin "1") (pinfunction "S_1") (pintype "passive"))
      (node (ref "S1") (pin "2") (pinfunction "S1_2") (pintype "passive"))
      (node (ref "U4") (pin "2") (pinfunction "~{RESIN}_2") (pintype "input"))
    )
    (net (code "77") (name "Net-(U4-CT)") (class "Default")
      (node (ref "R4") (pin "2") (pinfunction "2_2") (pintype "passive"))
      (node (ref "U4") (pin "3") (pinfunction "CT_3") (pintype "input"))
    )
    (net (code "78") (name "Net-(U4-REF)") (class "Default")
      (node (ref "C18") (pin "1") (pinfunction "1_1") (pintype "passive"))
      (node (ref "U4") (pin "1") (pinfunction "REF_1") (pintype "bidirectional"))
    )
    (net (code "79") (name "Net-(U4-RESET)") (class "Default")
      (node (ref "R3") (pin "2") (pinfunction "2_2") (pintype "passive"))
      (node (ref "U4") (pin "6") (pinfunction "RESET_6") (pintype "open_collector"))
    )
    (net (code "80") (name "Net-(U6A-Y0)") (class "Default")
      (node (ref "U6") (pin "15") (pinfunction "Y0_15") (pintype "output"))
      (node (ref "U8") (pin "1") (pinfunction "I0_1") (pintype "input"))
    )
    (net (code "81") (name "Net-(U6A-Y1)") (class "Default")
      (node (ref "U6") (pin "14") (pinfunction "Y1_14") (pintype "output"))
      (node (ref "U8") (pin "2") (pinfunction "I1_2") (pintype "input"))
    )
    (net (code "82") (name "Net-(U6A-Y2)") (class "Default")
      (node (ref "U6") (pin "13") (pinfunction "Y2_13") (pintype "output"))
      (node (ref "U8") (pin "13") (pinfunction "I2_13") (pintype "input"))
    )
    (net (code "83") (name "Net-(U7A-PRE)") (class "Default")
      (node (ref "U7") (pin "4") (pinfunction "PRE_4") (pintype "input"))
      (node (ref "U7") (pin "9") (pinfunction "Q_9") (pintype "output"))
    )
    (net (code "84") (name "Net-(U7A-Q)") (class "Default")
      (node (ref "U7") (pin "12") (pinfunction "D_12") (pintype "input"))
      (node (ref "U7") (pin "5") (pinfunction "Q_5") (pintype "output"))
    )
    (net (code "85") (name "Net-(U9D-O)") (class "Default")
      (node (ref "LD1") (pin "AR") (pinfunction "AR_AR") (pintype "passive"))
      (node (ref "U9") (pin "13") (pinfunction "O_13") (pintype "output"))
    )
    (net (code "86") (name "Net-(U10A-I1)") (class "Default")
      (node (ref "U10") (pin "2") (pinfunction "I1_2") (pintype "input"))
      (node (ref "U11") (pin "3") (pinfunction "O_3") (pintype "output"))
    )
    (net (code "87") (name "Net-(U10B-I1)") (class "Default")
      (node (ref "U10") (pin "5") (pinfunction "I1_5") (pintype "input"))
      (node (ref "U8") (pin "6") (pinfunction "O_6") (pintype "output"))
    )
    (net (code "88") (name "Net-(U10B-O)") (class "Default")
      (node (ref "U10") (pin "6") (pinfunction "O_6") (pintype "output"))
      (node (ref "U11") (pin "2") (pinfunction "I1_2") (pintype "input"))
    )
    (net (code "89") (name "unconnected-(BUSG-S-Pad15)") (class "Default")
      (node (ref "BUS") (pin "15") (pinfunction "S_15") (pintype "passive"))
    )
    (net (code "90") (name "unconnected-(BUSH-S-Pad16)") (class "Default")
      (node (ref "BUS") (pin "16") (pinfunction "S_16") (pintype "passive"))
    )
    (net (code "91") (name "unconnected-(BUSI-S-Pad17)") (class "Default")
      (node (ref "BUS") (pin "17") (pinfunction "S_17") (pintype "passive"))
    )
    (net (code "92") (name "unconnected-(BUSJ-S-Pad18)") (class "Default")
      (node (ref "BUS") (pin "18") (pinfunction "S_18") (pintype "passive"))
    )
    (net (code "93") (name "unconnected-(BUSK-S-Pad19)") (class "Default")
      (node (ref "BUS") (pin "19") (pinfunction "S_19") (pintype "passive"))
    )
    (net (code "94") (name "unconnected-(BUSM-S-Pad20)") (class "Default")
      (node (ref "BUS") (pin "20") (pinfunction "S_20") (pintype "passive"))
    )
    (net (code "95") (name "unconnected-(BUSN-S-Pad21)") (class "Default")
      (node (ref "BUS") (pin "21") (pinfunction "S_21") (pintype "passive"))
    )
    (net (code "96") (name "unconnected-(BUSO-S-Pad22)") (class "Default")
      (node (ref "BUS") (pin "22") (pinfunction "S_22") (pintype "passive"))
    )
    (net (code "97") (name "unconnected-(J1-Pad2)") (class "Default")
      (node (ref "J1") (pin "2") (pinfunction "2_2") (pintype "passive"))
    )
    (net (code "98") (name "unconnected-(QG1-TS-Pad1)") (class "Default")
      (node (ref "QG1") (pin "1") (pinfunction "TS_1") (pintype "passive"))
    )
    (net (code "99") (name "unconnected-(U3A-A6-Pad7)") (class "Default")
      (node (ref "U3") (pin "7") (pinfunction "A6_7") (pintype "bidirectional"))
    )
    (net (code "100") (name "unconnected-(U3A-A7-Pad8)") (class "Default")
      (node (ref "U3") (pin "8") (pinfunction "A7_8") (pintype "bidirectional"))
    )
    (net (code "101") (name "unconnected-(U5-BUSAK-Pad23)") (class "Default")
      (node (ref "U5") (pin "23") (pinfunction "BUSAK_23") (pintype "output"))
    )
    (net (code "102") (name "unconnected-(U6A-Y3-Pad12)") (class "Default")
      (node (ref "U6") (pin "12") (pinfunction "Y3_12") (pintype "output"))
    )
    (net (code "103") (name "unconnected-(U6A-Y5-Pad10)") (class "Default")
      (node (ref "U6") (pin "10") (pinfunction "Y5_10") (pintype "output"))
    )
    (net (code "104") (name "unconnected-(U7B-~{Q}-Pad8)") (class "Default")
      (node (ref "U7") (pin "8") (pinfunction "~{Q}_8") (pintype "output"))
    )
    (net (code "105") (name "unconnected-(U8C-O-Pad8)") (class "Default")
      (node (ref "U8") (pin "8") (pinfunction "O_8") (pintype "output"))
    )
    (net (code "106") (name "unconnected-(U9A-O-Pad1)") (class "Default")
      (node (ref "U9") (pin "1") (pinfunction "O_1") (pintype "output"))
    )
    (net (code "107") (name "unconnected-(U9B-O-Pad4)") (class "Default")
      (node (ref "U9") (pin "4") (pinfunction "O_4") (pintype "output"))
    )
    (net (code "108") (name "unconnected-(U9C-O-Pad10)") (class "Default")
      (node (ref "U9") (pin "10") (pinfunction "O_10") (pintype "output"))
    )
    (net (code "109") (name "unconnected-(U10C-O-Pad8)") (class "Default")
      (node (ref "U10") (pin "8") (pinfunction "O_8") (pintype "output"))
    )
    (net (code "110") (name "unconnected-(U10D-O-Pad11)") (class "Default")
      (node (ref "U10") (pin "11") (pinfunction "O_11") (pintype "output"))
    )
    (net (code "111") (name "unconnected-(U11C-O-Pad8)") (class "Default")
      (node (ref "U11") (pin "8") (pinfunction "O_8") (pintype "output"))
    )
    (net (code "112") (name "unconnected-(U11D-O-Pad11)") (class "Default")
      (node (ref "U11") (pin "11") (pinfunction "O_11") (pintype "output"))
    )
    (net (code "113") (name "~{APP_ROM_CS}") (class "Default")
      (node (ref "U10") (pin "4") (pinfunction "I0_4") (pintype "input"))
      (node (ref "U12") (pin "22") (pinfunction "~{CE}_22") (pintype "input"))
      (node (ref "U7") (pin "2") (pinfunction "D_2") (pintype "input"))
      (node (ref "U8") (pin "12") (pinfunction "O_12") (pintype "output"))
    )
    (net (code "114") (name "~{BUSRQ}") (class "Default")
      (node (ref "R14") (pin "2") (pinfunction "2_2") (pintype "passive"))
      (node (ref "U5") (pin "25") (pinfunction "BUSRQ_25") (pintype "input"))
    )
    (net (code "115") (name "~{CHAR_ROM_CS}") (class "Default")
      (node (ref "U15") (pin "22") (pinfunction "~{CE}_22") (pintype "input"))
      (node (ref "U6") (pin "7") (pinfunction "Y7_7") (pintype "output"))
      (node (ref "U8") (pin "5") (pinfunction "I2_5") (pintype "input"))
    )
    (net (code "116") (name "~{HALT}") (class "Default")
      (node (ref "U11") (pin "4") (pinfunction "I0_4") (pintype "input"))
      (node (ref "U11") (pin "5") (pinfunction "I1_5") (pintype "input"))
      (node (ref "U5") (pin "18") (pinfunction "HALT_18") (pintype "output"))
      (node (ref "U9") (pin "11") (pinfunction "I0_11") (pintype "input"))
      (node (ref "U9") (pin "12") (pinfunction "I1_12") (pintype "input"))
    )
    (net (code "117") (name "~{INT}") (class "Default")
      (node (ref "BUS") (pin "11") (pinfunction "S_11") (pintype "passive"))
      (node (ref "R12") (pin "2") (pinfunction "2_2") (pintype "passive"))
      (node (ref "U5") (pin "16") (pinfunction "INT_16") (pintype "input"))
    )
    (net (code "118") (name "~{IORQ}") (class "Default")
      (node (ref "R7") (pin "2") (pinfunction "2_2") (pintype "passive"))
      (node (ref "U3") (pin "16") (pinfunction "B3_16") (pintype "bidirectional"))
      (node (ref "U5") (pin "20") (pinfunction "IORQ_20") (pintype "output"))
    )
    (net (code "119") (name "~{M1}") (class "Default")
      (node (ref "R5") (pin "2") (pinfunction "2_2") (pintype "passive"))
      (node (ref "U3") (pin "18") (pinfunction "B1_18") (pintype "bidirectional"))
      (node (ref "U5") (pin "27") (pinfunction "M1_27") (pintype "output"))
    )
    (net (code "120") (name "~{MREQ}") (class "Default")
      (node (ref "R6") (pin "2") (pinfunction "2_2") (pintype "passive"))
      (node (ref "U3") (pin "17") (pinfunction "B2_17") (pintype "bidirectional"))
      (node (ref "U5") (pin "19") (pinfunction "MREQ_19") (pintype "output"))
      (node (ref "U6") (pin "4") (pinfunction "G2A_4") (pintype "input"))
    )
    (net (code "121") (name "~{NMI}") (class "Default")
      (node (ref "BUS") (pin "12") (pinfunction "S_12") (pintype "passive"))
      (node (ref "R13") (pin "2") (pinfunction "2_2") (pintype "passive"))
      (node (ref "U5") (pin "17") (pinfunction "NMI_17") (pintype "input"))
    )
    (net (code "122") (name "~{RAM_CS}") (class "Default")
      (node (ref "U13") (pin "20") (pinfunction "~{CE}_20") (pintype "input"))
      (node (ref "U6") (pin "11") (pinfunction "Y4_11") (pintype "output"))
      (node (ref "U8") (pin "3") (pinfunction "I0_3") (pintype "input"))
    )
    (net (code "123") (name "~{RD}") (class "Default")
      (node (ref "R8") (pin "2") (pinfunction "2_2") (pintype "passive"))
      (node (ref "U11") (pin "1") (pinfunction "I0_1") (pintype "input"))
      (node (ref "U12") (pin "24") (pinfunction "~{OE}_24") (pintype "input"))
      (node (ref "U13") (pin "22") (pinfunction "~{OE}_22") (pintype "input"))
      (node (ref "U14") (pin "24") (pinfunction "~{OE}_24") (pintype "input"))
      (node (ref "U15") (pin "24") (pinfunction "~{OE}_24") (pintype "input"))
      (node (ref "U3") (pin "15") (pinfunction "B4_15") (pintype "bidirectional"))
      (node (ref "U5") (pin "21") (pinfunction "RD_21") (pintype "output"))
    )
    (net (code "124") (name "~{RESET}") (class "Default")
      (node (ref "BUS") (pin "6") (pinfunction "S_6") (pintype "passive"))
      (node (ref "R2") (pin "2") (pinfunction "2_2") (pintype "passive"))
      (node (ref "U4") (pin "5") (pinfunction "~{RESET}_5") (pintype "open_collector"))
      (node (ref "U5") (pin "26") (pinfunction "RESET_26") (pintype "input"))
    )
    (net (code "125") (name "~{RFSH}") (class "Default")
      (node (ref "R10") (pin "2") (pinfunction "2_2") (pintype "passive"))
      (node (ref "U5") (pin "28") (pinfunction "RFSH_28") (pintype "output"))
      (node (ref "U6") (pin "6") (pinfunction "G1_6") (pintype "input"))
    )
    (net (code "126") (name "~{TZ_ROM_CS}") (class "Default")
      (node (ref "U14") (pin "22") (pinfunction "~{CE}_22") (pintype "input"))
      (node (ref "U6") (pin "9") (pinfunction "Y6_9") (pintype "output"))
      (node (ref "U8") (pin "4") (pinfunction "I1_4") (pintype "input"))
    )
    (net (code "127") (name "~{WAIT}") (class "Default")
      (node (ref "BUS") (pin "10") (pinfunction "S_10") (pintype "passive"))
      (node (ref "JP1") (pin "2") (pinfunction "2_2") (pintype "passive"))
      (node (ref "R11") (pin "2") (pinfunction "2_2") (pintype "passive"))
      (node (ref "U5") (pin "24") (pinfunction "WAIT_24") (pintype "input"))
    )
    (net (code "128") (name "~{WR}") (class "Default")
      (node (ref "R9") (pin "2") (pinfunction "2_2") (pintype "passive"))
      (node (ref "U10") (pin "1") (pinfunction "I0_1") (pintype "input"))
      (node (ref "U12") (pin "31") (pinfunction "~{WE}_31") (pintype "input"))
      (node (ref "U13") (pin "27") (pinfunction "~{WE}_27") (pintype "input"))
      (node (ref "U14") (pin "31") (pinfunction "~{WE}_31") (pintype "input"))
      (node (ref "U15") (pin "31") (pinfunction "~{WE}_31") (pintype "input"))
      (node (ref "U3") (pin "14") (pinfunction "B5_14") (pintype "bidirectional"))
      (node (ref "U5") (pin "22") (pinfunction "WR_22") (pintype "output"))
    )
  )
)
